# E46_Driver_Board_-_Full_Design.net
KiCad netlist of a schematic drawn in EAGLE
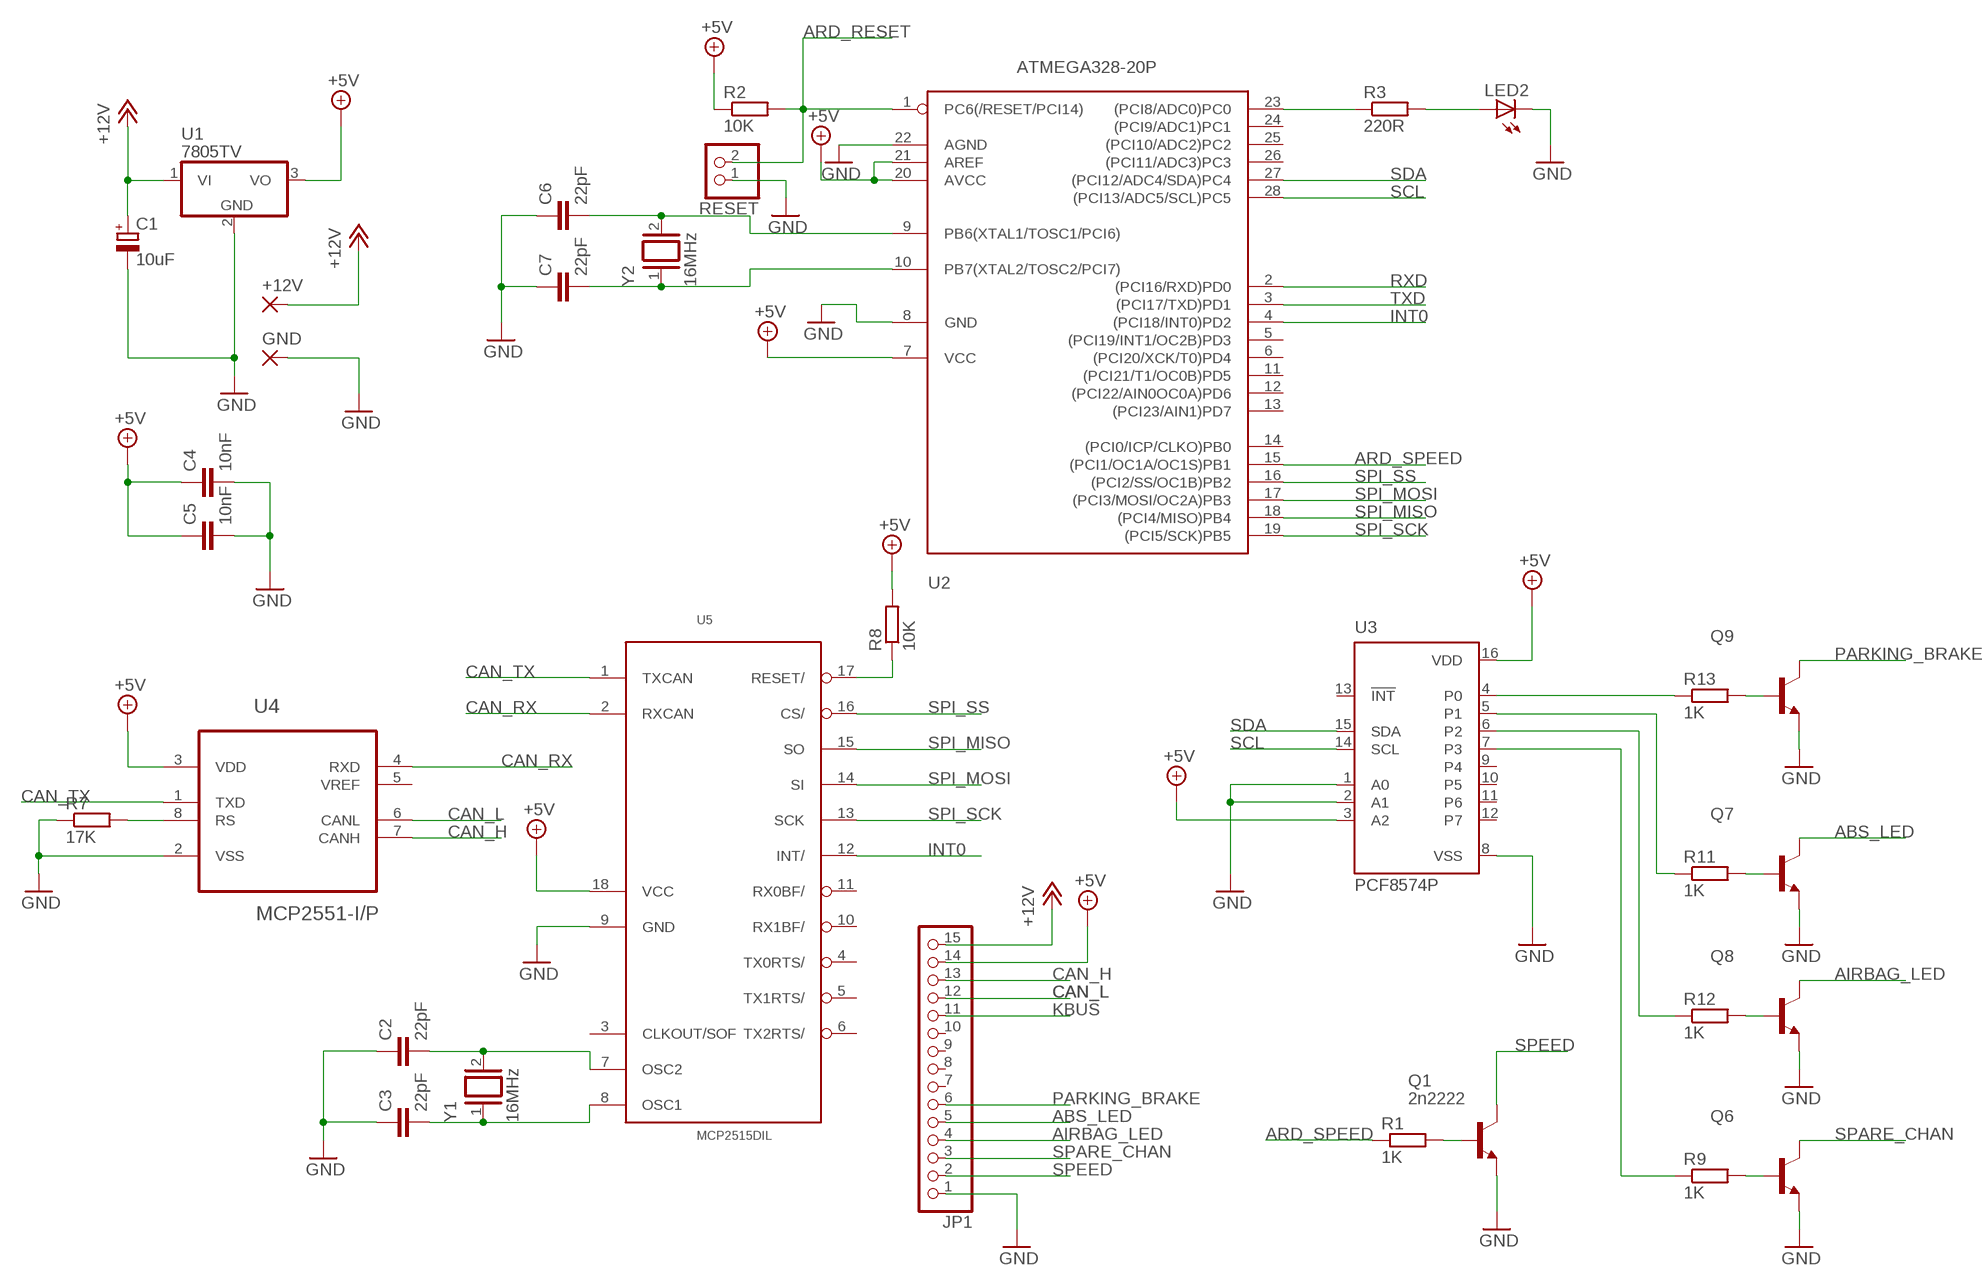
[diagram p0: schematic, sheet 1]

(export (version "E")
  (design (tool "Eeschema 10.0.6"))
  (components
    (comp (ref "+12V")
      (value "2,54/1,1")
      (footprint "eagle-import:2,54_1,1")
      (libsource (lib "eagle-import") (part "2,54/1,1"))
    )
    (comp (ref "C1")
      (value "10uF")
      (footprint "eagle-import:E3,5-8")
      (libsource (lib "eagle-import") (part "CPOL-EUE3.5-8"))
    )
    (comp (ref "C2")
      (value "22pF")
      (footprint "eagle-import:C025-024X044")
      (libsource (lib "eagle-import") (part "C-EU025-024X044"))
    )
    (comp (ref "C3")
      (value "22pF")
      (footprint "eagle-import:C025-024X044")
      (libsource (lib "eagle-import") (part "C-EU025-024X044"))
    )
    (comp (ref "C4")
      (value "10nF")
      (footprint "eagle-import:C025-024X044")
      (libsource (lib "eagle-import") (part "C-EU025-024X044"))
    )
    (comp (ref "C5")
      (value "10nF")
      (footprint "eagle-import:C025-024X044")
      (libsource (lib "eagle-import") (part "C-EU025-024X044"))
    )
    (comp (ref "C6")
      (value "22pF")
      (footprint "eagle-import:C025-024X044")
      (libsource (lib "eagle-import") (part "C-EU025-024X044"))
    )
    (comp (ref "C7")
      (value "22pF")
      (footprint "eagle-import:C025-024X044")
      (libsource (lib "eagle-import") (part "C-EU025-024X044"))
    )
    (comp (ref "GND")
      (value "2,54/1,1")
      (footprint "eagle-import:2,54_1,1")
      (libsource (lib "eagle-import") (part "2,54/1,1"))
    )
    (comp (ref "JP1")
      (value "PINHD-1X15")
      (footprint "eagle-import:1X15")
      (libsource (lib "eagle-import") (part "PINHD-1X15"))
    )
    (comp (ref "LED2")
      (value "LED5MM")
      (footprint "eagle-import:LED5MM")
      (libsource (lib "eagle-import") (part "LED5MM"))
    )
    (comp (ref "Q1")
      (value "2n2222")
      (footprint "eagle-import:TO92-EBC")
      (libsource (lib "eagle-import") (part "-NPN-TO92-EBC2N2222"))
    )
    (comp (ref "Q6")
      (value "2N2222-NPN-TO92-EBC")
      (footprint "eagle-import:TO92-EBC")
      (libsource (lib "eagle-import") (part "-NPN-TO92-EBC2N2222"))
    )
    (comp (ref "Q7")
      (value "2N2222-NPN-TO92-EBC")
      (footprint "eagle-import:TO92-EBC")
      (libsource (lib "eagle-import") (part "-NPN-TO92-EBC2N2222"))
    )
    (comp (ref "Q8")
      (value "2N2222-NPN-TO92-EBC")
      (footprint "eagle-import:TO92-EBC")
      (libsource (lib "eagle-import") (part "-NPN-TO92-EBC2N2222"))
    )
    (comp (ref "Q9")
      (value "2N2222-NPN-TO92-EBC")
      (footprint "eagle-import:TO92-EBC")
      (libsource (lib "eagle-import") (part "-NPN-TO92-EBC2N2222"))
    )
    (comp (ref "R1")
      (value "1K")
      (footprint "eagle-import:0204_5")
      (libsource (lib "eagle-import") (part "R-EU_0204/5"))
    )
    (comp (ref "R2")
      (value "10K")
      (footprint "eagle-import:0204_5")
      (libsource (lib "eagle-import") (part "R-EU_0204/5"))
    )
    (comp (ref "R3")
      (value "220R")
      (footprint "eagle-import:0204_5")
      (libsource (lib "eagle-import") (part "R-EU_0204/5"))
    )
    (comp (ref "R7")
      (value "17K")
      (footprint "eagle-import:0204_5")
      (libsource (lib "eagle-import") (part "R-EU_0204/5"))
    )
    (comp (ref "R8")
      (value "10K")
      (footprint "eagle-import:0204_5")
      (libsource (lib "eagle-import") (part "R-EU_0204/5"))
    )
    (comp (ref "R9")
      (value "1K")
      (footprint "eagle-import:0204_5")
      (libsource (lib "eagle-import") (part "R-EU_0204/5"))
    )
    (comp (ref "R11")
      (value "1K")
      (footprint "eagle-import:0204_5")
      (libsource (lib "eagle-import") (part "R-EU_0204/5"))
    )
    (comp (ref "R12")
      (value "1K")
      (footprint "eagle-import:0204_5")
      (libsource (lib "eagle-import") (part "R-EU_0204/5"))
    )
    (comp (ref "R13")
      (value "1K")
      (footprint "eagle-import:0204_5")
      (libsource (lib "eagle-import") (part "R-EU_0204/5"))
    )
    (comp (ref "RESET")
      (value "PINHD-1X2")
      (footprint "eagle-import:1X02")
      (libsource (lib "eagle-import") (part "PINHD-1X2"))
    )
    (comp (ref "U1")
      (value "7805TV")
      (footprint "eagle-import:TO220V")
      (libsource (lib "eagle-import") (part "78TV05"))
    )
    (comp (ref "U2")
      (value "ATMEGA328-20P")
      (footprint "eagle-import:DIL28-3")
      (libsource (lib "eagle-import") (part "ATMEGA328P-20"))
    )
    (comp (ref "U3")
      (value "PCF8574P")
      (footprint "eagle-import:DIL16")
      (fields (field (name "MPN") "PCF8574PN"))
      (libsource (lib "eagle-import") (part "PCF8574P"))
    )
    (comp (ref "U4")
      (value "MCP2551-I/P")
      (footprint "eagle-import:DIP254P762X432-8")
      (libsource (lib "eagle-import") (part "MCP2551-I/P"))
    )
    (comp (ref "U5")
      (value "MCP2515DIL")
      (footprint "eagle-import:DIL18")
      (libsource (lib "eagle-import") (part "MCP2515DIL"))
    )
    (comp (ref "Y1")
      (value "16MHz")
      (footprint "eagle-import:QS")
      (libsource (lib "eagle-import") (part "XTAL/S"))
    )
    (comp (ref "Y2")
      (value "16MHz")
      (footprint "eagle-import:QS")
      (libsource (lib "eagle-import") (part "XTAL/S"))
    )
  )
  (nets
    (net (code "1") (name "+5V") (class "Default")
      (node (ref "C4") (pin "1") (pinfunction "1_1") (pintype "passive"))
      (node (ref "C5") (pin "1") (pinfunction "1_1") (pintype "passive"))
      (node (ref "JP1") (pin "14") (pinfunction "14_14") (pintype "passive"))
      (node (ref "R2") (pin "1") (pinfunction "1_1") (pintype "passive"))
      (node (ref "R8") (pin "2") (pinfunction "2_2") (pintype "passive"))
      (node (ref "U1") (pin "3") (pinfunction "VO_3") (pintype "passive"))
      (node (ref "U2") (pin "20") (pinfunction "AVCC_20") (pintype "bidirectional"))
      (node (ref "U2") (pin "21") (pinfunction "AREF_21") (pintype "bidirectional"))
      (node (ref "U2") (pin "7") (pinfunction "VCC_7") (pintype "bidirectional"))
      (node (ref "U3") (pin "16") (pinfunction "VDD_16") (pintype "power_in"))
      (node (ref "U3") (pin "3") (pinfunction "A2_3") (pintype "input"))
      (node (ref "U4") (pin "3") (pinfunction "VDD_3") (pintype "power_in"))
      (node (ref "U5") (pin "18") (pinfunction "VCC_18") (pintype "power_in"))
    )
    (net (code "2") (name "+12V") (class "Default")
      (node (ref "+12V") (pin "1") (pinfunction "P_1") (pintype "passive"))
      (node (ref "C1") (pin "+") (pinfunction "+_+") (pintype "passive"))
      (node (ref "JP1") (pin "15") (pinfunction "15_15") (pintype "passive"))
      (node (ref "U1") (pin "1") (pinfunction "VI_1") (pintype "input"))
    )
    (net (code "3") (name "/ABS_LED") (class "Default")
      (node (ref "JP1") (pin "5") (pinfunction "5_5") (pintype "passive"))
      (node (ref "Q7") (pin "C") (pinfunction "C_C") (pintype "passive"))
    )
    (net (code "4") (name "/AIRBAG_LED") (class "Default")
      (node (ref "JP1") (pin "4") (pinfunction "4_4") (pintype "passive"))
      (node (ref "Q8") (pin "C") (pinfunction "C_C") (pintype "passive"))
    )
    (net (code "5") (name "/ARD_RESET") (class "Default")
      (node (ref "R2") (pin "2") (pinfunction "2_2") (pintype "passive"))
      (node (ref "RESET") (pin "2") (pinfunction "2_2") (pintype "passive"))
      (node (ref "U2") (pin "1") (pinfunction "PC6(/RESET/PCI14)_1") (pintype "bidirectional"))
    )
    (net (code "6") (name "/ARD_SPEED") (class "Default")
      (node (ref "R1") (pin "1") (pinfunction "1_1") (pintype "passive"))
      (node (ref "U2") (pin "15") (pinfunction "(PCI1/OC1A/OC1S)PB1_15") (pintype "bidirectional"))
    )
    (net (code "7") (name "/CAN_H") (class "Default")
      (node (ref "JP1") (pin "13") (pinfunction "13_13") (pintype "passive"))
      (node (ref "U4") (pin "7") (pinfunction "CANH_7") (pintype "bidirectional"))
    )
    (net (code "8") (name "/CAN_L") (class "Default")
      (node (ref "JP1") (pin "12") (pinfunction "12_12") (pintype "passive"))
      (node (ref "U4") (pin "6") (pinfunction "CANL_6") (pintype "bidirectional"))
    )
    (net (code "9") (name "/CAN_RX") (class "Default")
      (node (ref "U4") (pin "4") (pinfunction "RXD_4") (pintype "output"))
      (node (ref "U5") (pin "2") (pinfunction "RXCAN_2") (pintype "input"))
    )
    (net (code "10") (name "/CAN_TX") (class "Default")
      (node (ref "U4") (pin "1") (pinfunction "TXD_1") (pintype "input"))
      (node (ref "U5") (pin "1") (pinfunction "TXCAN_1") (pintype "output"))
    )
    (net (code "11") (name "/INT0") (class "Default")
      (node (ref "U2") (pin "4") (pinfunction "(PCI18/INT0)PD2_4") (pintype "bidirectional"))
      (node (ref "U5") (pin "12") (pinfunction "INT/_12") (pintype "output"))
    )
    (net (code "12") (name "/KBUS") (class "Default")
      (node (ref "JP1") (pin "11") (pinfunction "11_11") (pintype "passive"))
    )
    (net (code "13") (name "/PARKING_BRAKE") (class "Default")
      (node (ref "JP1") (pin "6") (pinfunction "6_6") (pintype "passive"))
      (node (ref "Q9") (pin "C") (pinfunction "C_C") (pintype "passive"))
    )
    (net (code "14") (name "/RXD") (class "Default")
      (node (ref "U2") (pin "2") (pinfunction "(PCI16/RXD)PD0_2") (pintype "bidirectional"))
    )
    (net (code "15") (name "/SCL") (class "Default")
      (node (ref "U2") (pin "28") (pinfunction "(PCI13/ADC5/SCL)PC5_28") (pintype "bidirectional"))
      (node (ref "U3") (pin "14") (pinfunction "SCL_14") (pintype "input"))
    )
    (net (code "16") (name "/SDA") (class "Default")
      (node (ref "U2") (pin "27") (pinfunction "(PCI12/ADC4/SDA)PC4_27") (pintype "bidirectional"))
      (node (ref "U3") (pin "15") (pinfunction "SDA_15") (pintype "bidirectional"))
    )
    (net (code "17") (name "/SPARE_CHAN") (class "Default")
      (node (ref "JP1") (pin "3") (pinfunction "3_3") (pintype "passive"))
      (node (ref "Q6") (pin "C") (pinfunction "C_C") (pintype "passive"))
    )
    (net (code "18") (name "/SPEED") (class "Default")
      (node (ref "JP1") (pin "2") (pinfunction "2_2") (pintype "passive"))
      (node (ref "Q1") (pin "C") (pinfunction "C_C") (pintype "passive"))
    )
    (net (code "19") (name "/SPI_MISO") (class "Default")
      (node (ref "U2") (pin "18") (pinfunction "(PCI4/MISO)PB4_18") (pintype "bidirectional"))
      (node (ref "U5") (pin "15") (pinfunction "SO_15") (pintype "output"))
    )
    (net (code "20") (name "/SPI_MOSI") (class "Default")
      (node (ref "U2") (pin "17") (pinfunction "(PCI3/MOSI/OC2A)PB3_17") (pintype "bidirectional"))
      (node (ref "U5") (pin "14") (pinfunction "SI_14") (pintype "input"))
    )
    (net (code "21") (name "/SPI_SCK") (class "Default")
      (node (ref "U2") (pin "19") (pinfunction "(PCI5/SCK)PB5_19") (pintype "bidirectional"))
      (node (ref "U5") (pin "13") (pinfunction "SCK_13") (pintype "input"))
    )
    (net (code "22") (name "/SPI_SS") (class "Default")
      (node (ref "U2") (pin "16") (pinfunction "(PCI2/SS/OC1B)PB2_16") (pintype "bidirectional"))
      (node (ref "U5") (pin "16") (pinfunction "CS/_16") (pintype "input"))
    )
    (net (code "23") (name "/TXD") (class "Default")
      (node (ref "U2") (pin "3") (pinfunction "(PCI17/TXD)PD1_3") (pintype "bidirectional"))
    )
    (net (code "24") (name "GND") (class "Default")
      (node (ref "C1") (pin "-") (pinfunction "-_-") (pintype "passive"))
      (node (ref "C2") (pin "1") (pinfunction "1_1") (pintype "passive"))
      (node (ref "C3") (pin "1") (pinfunction "1_1") (pintype "passive"))
      (node (ref "C4") (pin "2") (pinfunction "2_2") (pintype "passive"))
      (node (ref "C5") (pin "2") (pinfunction "2_2") (pintype "passive"))
      (node (ref "C6") (pin "1") (pinfunction "1_1") (pintype "passive"))
      (node (ref "C7") (pin "1") (pinfunction "1_1") (pintype "passive"))
      (node (ref "GND") (pin "1") (pinfunction "P_1") (pintype "passive"))
      (node (ref "JP1") (pin "1") (pinfunction "1_1") (pintype "passive"))
      (node (ref "LED2") (pin "K") (pinfunction "C_K") (pintype "passive"))
      (node (ref "Q1") (pin "E") (pinfunction "E_E") (pintype "passive"))
      (node (ref "Q6") (pin "E") (pinfunction "E_E") (pintype "passive"))
      (node (ref "Q7") (pin "E") (pinfunction "E_E") (pintype "passive"))
      (node (ref "Q8") (pin "E") (pinfunction "E_E") (pintype "passive"))
      (node (ref "Q9") (pin "E") (pinfunction "E_E") (pintype "passive"))
      (node (ref "R7") (pin "1") (pinfunction "1_1") (pintype "passive"))
      (node (ref "RESET") (pin "1") (pinfunction "1_1") (pintype "passive"))
      (node (ref "U1") (pin "2") (pinfunction "GND_2") (pintype "passive"))
      (node (ref "U2") (pin "22") (pinfunction "AGND_22") (pintype "bidirectional"))
      (node (ref "U2") (pin "8") (pinfunction "GND_8") (pintype "bidirectional"))
      (node (ref "U3") (pin "1") (pinfunction "A0_1") (pintype "input"))
      (node (ref "U3") (pin "2") (pinfunction "A1_2") (pintype "input"))
      (node (ref "U3") (pin "8") (pinfunction "VSS_8") (pintype "power_in"))
      (node (ref "U4") (pin "2") (pinfunction "VSS_2") (pintype "power_in"))
      (node (ref "U5") (pin "9") (pinfunction "GND_9") (pintype "power_in"))
    )
    (net (code "25") (name "Net-(LED2-PadA)") (class "Default")
      (node (ref "LED2") (pin "A") (pinfunction "A_A") (pintype "passive"))
      (node (ref "R3") (pin "2") (pinfunction "2_2") (pintype "passive"))
    )
    (net (code "26") (name "Net-(Q1-PadB)") (class "Default")
      (node (ref "Q1") (pin "B") (pinfunction "B_B") (pintype "passive"))
      (node (ref "R1") (pin "2") (pinfunction "2_2") (pintype "passive"))
    )
    (net (code "27") (name "Net-(Q6-PadB)") (class "Default")
      (node (ref "Q6") (pin "B") (pinfunction "B_B") (pintype "passive"))
      (node (ref "R9") (pin "2") (pinfunction "2_2") (pintype "passive"))
    )
    (net (code "28") (name "Net-(Q7-PadB)") (class "Default")
      (node (ref "Q7") (pin "B") (pinfunction "B_B") (pintype "passive"))
      (node (ref "R11") (pin "2") (pinfunction "2_2") (pintype "passive"))
    )
    (net (code "29") (name "Net-(Q8-PadB)") (class "Default")
      (node (ref "Q8") (pin "B") (pinfunction "B_B") (pintype "passive"))
      (node (ref "R12") (pin "2") (pinfunction "2_2") (pintype "passive"))
    )
    (net (code "30") (name "Net-(Q9-PadB)") (class "Default")
      (node (ref "Q9") (pin "B") (pinfunction "B_B") (pintype "passive"))
      (node (ref "R13") (pin "2") (pinfunction "2_2") (pintype "passive"))
    )
    (net (code "31") (name "Net-(U2-(PCI8{slash}ADC0)PC0)") (class "Default")
      (node (ref "R3") (pin "1") (pinfunction "1_1") (pintype "passive"))
      (node (ref "U2") (pin "23") (pinfunction "(PCI8/ADC0)PC0_23") (pintype "bidirectional"))
    )
    (net (code "32") (name "Net-(U2-PB6(XTAL1{slash}TOSC1{slash}PCI6))") (class "Default")
      (node (ref "C6") (pin "2") (pinfunction "2_2") (pintype "passive"))
      (node (ref "U2") (pin "9") (pinfunction "PB6(XTAL1/TOSC1/PCI6)_9") (pintype "bidirectional"))
      (node (ref "Y2") (pin "2") (pinfunction "2_2") (pintype "passive"))
    )
    (net (code "33") (name "Net-(U2-PB7(XTAL2{slash}TOSC2{slash}PCI7))") (class "Default")
      (node (ref "C7") (pin "2") (pinfunction "2_2") (pintype "passive"))
      (node (ref "U2") (pin "10") (pinfunction "PB7(XTAL2/TOSC2/PCI7)_10") (pintype "bidirectional"))
      (node (ref "Y2") (pin "1") (pinfunction "1_1") (pintype "passive"))
    )
    (net (code "34") (name "Net-(U3-P0)") (class "Default")
      (node (ref "R13") (pin "1") (pinfunction "1_1") (pintype "passive"))
      (node (ref "U3") (pin "4") (pinfunction "P0_4") (pintype "bidirectional"))
    )
    (net (code "35") (name "Net-(U3-P1)") (class "Default")
      (node (ref "R11") (pin "1") (pinfunction "1_1") (pintype "passive"))
      (node (ref "U3") (pin "5") (pinfunction "P1_5") (pintype "bidirectional"))
    )
    (net (code "36") (name "Net-(U3-P2)") (class "Default")
      (node (ref "R12") (pin "1") (pinfunction "1_1") (pintype "passive"))
      (node (ref "U3") (pin "6") (pinfunction "P2_6") (pintype "bidirectional"))
    )
    (net (code "37") (name "Net-(U3-P3)") (class "Default")
      (node (ref "R9") (pin "1") (pinfunction "1_1") (pintype "passive"))
      (node (ref "U3") (pin "7") (pinfunction "P3_7") (pintype "bidirectional"))
    )
    (net (code "38") (name "Net-(U4-RS)") (class "Default")
      (node (ref "R7") (pin "2") (pinfunction "2_2") (pintype "passive"))
      (node (ref "U4") (pin "8") (pinfunction "RS_8") (pintype "input"))
    )
    (net (code "39") (name "Net-(U5-OSC1)") (class "Default")
      (node (ref "C3") (pin "2") (pinfunction "2_2") (pintype "passive"))
      (node (ref "U5") (pin "8") (pinfunction "OSC1_8") (pintype "bidirectional"))
      (node (ref "Y1") (pin "1") (pinfunction "1_1") (pintype "passive"))
    )
    (net (code "40") (name "Net-(U5-OSC2)") (class "Default")
      (node (ref "C2") (pin "2") (pinfunction "2_2") (pintype "passive"))
      (node (ref "U5") (pin "7") (pinfunction "OSC2_7") (pintype "bidirectional"))
      (node (ref "Y1") (pin "2") (pinfunction "2_2") (pintype "passive"))
    )
    (net (code "41") (name "Net-(U5-RESET{slash})") (class "Default")
      (node (ref "R8") (pin "1") (pinfunction "1_1") (pintype "passive"))
      (node (ref "U5") (pin "17") (pinfunction "RESET/_17") (pintype "input"))
    )
    (net (code "42") (name "unconnected-(JP1-Pad7)") (class "Default")
      (node (ref "JP1") (pin "7") (pinfunction "7_7") (pintype "passive"))
    )
    (net (code "43") (name "unconnected-(JP1-Pad8)") (class "Default")
      (node (ref "JP1") (pin "8") (pinfunction "8_8") (pintype "passive"))
    )
    (net (code "44") (name "unconnected-(JP1-Pad9)") (class "Default")
      (node (ref "JP1") (pin "9") (pinfunction "9_9") (pintype "passive"))
    )
    (net (code "45") (name "unconnected-(JP1-Pad10)") (class "Default")
      (node (ref "JP1") (pin "10") (pinfunction "10_10") (pintype "passive"))
    )
    (net (code "46") (name "unconnected-(U2-(PCI0{slash}ICP{slash}CLKO)PB0-Pad14)") (class "Default")
      (node (ref "U2") (pin "14") (pinfunction "(PCI0/ICP/CLKO)PB0_14") (pintype "bidirectional"))
    )
    (net (code "47") (name "unconnected-(U2-(PCI9{slash}ADC1)PC1-Pad24)") (class "Default")
      (node (ref "U2") (pin "24") (pinfunction "(PCI9/ADC1)PC1_24") (pintype "bidirectional"))
    )
    (net (code "48") (name "unconnected-(U2-(PCI10{slash}ADC2)PC2-Pad25)") (class "Default")
      (node (ref "U2") (pin "25") (pinfunction "(PCI10/ADC2)PC2_25") (pintype "bidirectional"))
    )
    (net (code "49") (name "unconnected-(U2-(PCI11{slash}ADC3)PC3-Pad26)") (class "Default")
      (node (ref "U2") (pin "26") (pinfunction "(PCI11/ADC3)PC3_26") (pintype "bidirectional"))
    )
    (net (code "50") (name "unconnected-(U2-(PCI19{slash}INT1{slash}OC2B)PD3-Pad5)") (class "Default")
      (node (ref "U2") (pin "5") (pinfunction "(PCI19/INT1/OC2B)PD3_5") (pintype "bidirectional"))
    )
    (net (code "51") (name "unconnected-(U2-(PCI20{slash}XCK{slash}T0)PD4-Pad6)") (class "Default")
      (node (ref "U2") (pin "6") (pinfunction "(PCI20/XCK/T0)PD4_6") (pintype "bidirectional"))
    )
    (net (code "52") (name "unconnected-(U2-(PCI21{slash}T1{slash}OC0B)PD5-Pad11)") (class "Default")
      (node (ref "U2") (pin "11") (pinfunction "(PCI21/T1/OC0B)PD5_11") (pintype "bidirectional"))
    )
    (net (code "53") (name "unconnected-(U2-(PCI22{slash}AIN0OC0A)PD6-Pad12)") (class "Default")
      (node (ref "U2") (pin "12") (pinfunction "(PCI22/AIN0OC0A)PD6_12") (pintype "bidirectional"))
    )
    (net (code "54") (name "unconnected-(U2-(PCI23{slash}AIN1)PD7-Pad13)") (class "Default")
      (node (ref "U2") (pin "13") (pinfunction "(PCI23/AIN1)PD7_13") (pintype "bidirectional"))
    )
    (net (code "55") (name "unconnected-(U3-P4-Pad9)") (class "Default")
      (node (ref "U3") (pin "9") (pinfunction "P4_9") (pintype "bidirectional"))
    )
    (net (code "56") (name "unconnected-(U3-P5-Pad10)") (class "Default")
      (node (ref "U3") (pin "10") (pinfunction "P5_10") (pintype "bidirectional"))
    )
    (net (code "57") (name "unconnected-(U3-P6-Pad11)") (class "Default")
      (node (ref "U3") (pin "11") (pinfunction "P6_11") (pintype "bidirectional"))
    )
    (net (code "58") (name "unconnected-(U3-P7-Pad12)") (class "Default")
      (node (ref "U3") (pin "12") (pinfunction "P7_12") (pintype "bidirectional"))
    )
    (net (code "59") (name "unconnected-(U3-~{INT}-Pad13)") (class "Default")
      (node (ref "U3") (pin "13") (pinfunction "~{INT}_13") (pintype "output"))
    )
    (net (code "60") (name "unconnected-(U4-VREF-Pad5)") (class "Default")
      (node (ref "U4") (pin "5") (pinfunction "VREF_5") (pintype "output"))
    )
    (net (code "61") (name "unconnected-(U5-CLKOUT{slash}SOF-Pad3)") (class "Default")
      (node (ref "U5") (pin "3") (pinfunction "CLKOUT/SOF_3") (pintype "bidirectional"))
    )
    (net (code "62") (name "unconnected-(U5-RX0BF{slash}-Pad11)") (class "Default")
      (node (ref "U5") (pin "11") (pinfunction "RX0BF/_11") (pintype "bidirectional"))
    )
    (net (code "63") (name "unconnected-(U5-RX1BF{slash}-Pad10)") (class "Default")
      (node (ref "U5") (pin "10") (pinfunction "RX1BF/_10") (pintype "bidirectional"))
    )
    (net (code "64") (name "unconnected-(U5-TX0RTS{slash}-Pad4)") (class "Default")
      (node (ref "U5") (pin "4") (pinfunction "TX0RTS/_4") (pintype "bidirectional"))
    )
    (net (code "65") (name "unconnected-(U5-TX1RTS{slash}-Pad5)") (class "Default")
      (node (ref "U5") (pin "5") (pinfunction "TX1RTS/_5") (pintype "bidirectional"))
    )
    (net (code "66") (name "unconnected-(U5-TX2RTS{slash}-Pad6)") (class "Default")
      (node (ref "U5") (pin "6") (pinfunction "TX2RTS/_6") (pintype "bidirectional"))
    )
  )
)
